# REV002.net
KiCad netlist of a schematic drawn in EAGLE
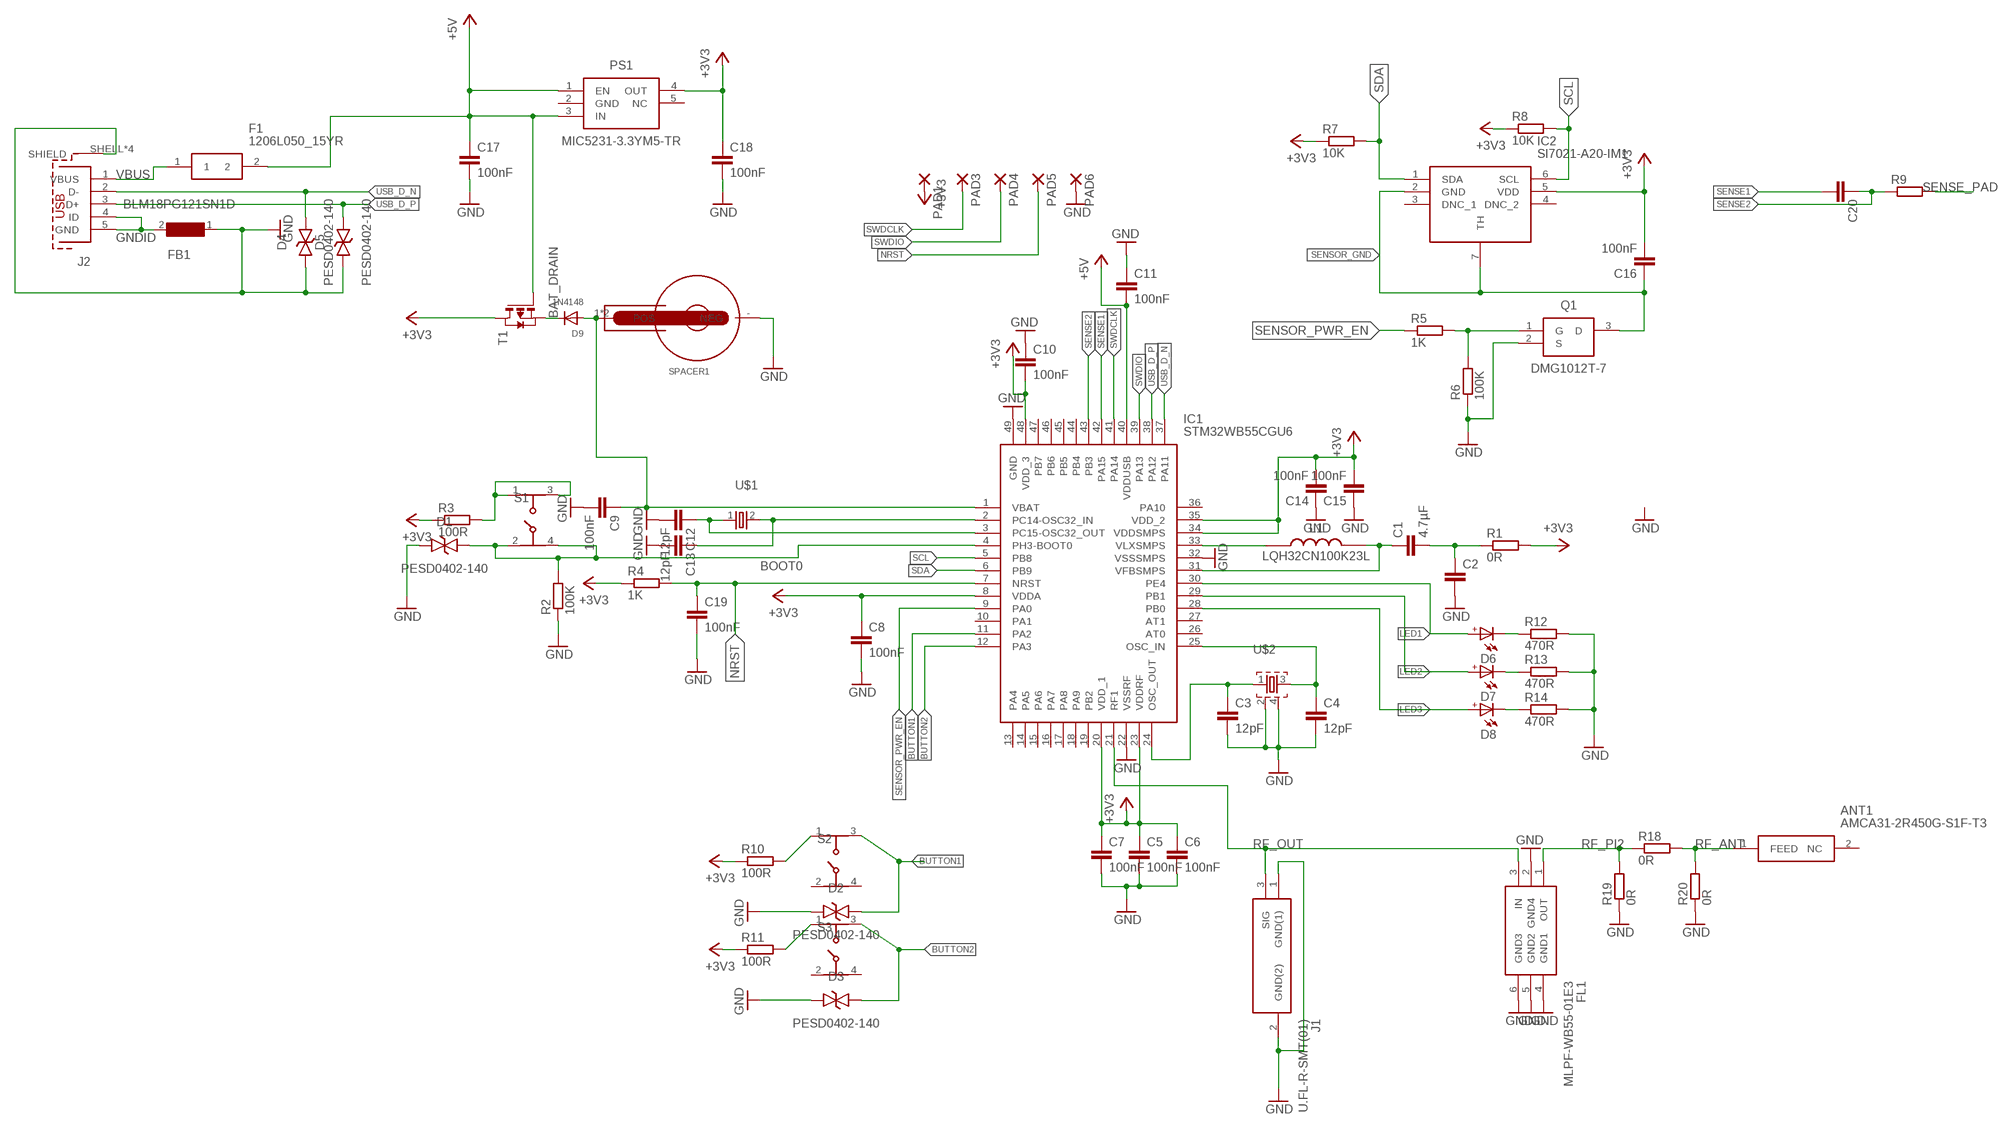
[diagram p0: schematic, sheet 1]

(export (version "E")
  (design (tool "Eeschema 10.0.6"))
  (components
    (comp (ref "ANT1")
      (value "AMCA31-2R450G-S1F-T3")
      (footprint "eagle-import:ANTC3216X140N")
      (libsource (lib "eagle-import") (part "AMCA31-2R450G-S1F-T3"))
    )
    (comp (ref "C1")
      (value "4.7µF")
      (footprint "eagle-import:C1210K")
      (libsource (lib "eagle-import") (part "C-EUC1210K"))
    )
    (comp (ref "C2")
      (value "C-EUC0402K")
      (footprint "eagle-import:C0402K")
      (libsource (lib "eagle-import") (part "C-EUC0402K"))
    )
    (comp (ref "C3")
      (value "12pF")
      (footprint "eagle-import:C0402K")
      (libsource (lib "eagle-import") (part "C-EUC0402K"))
    )
    (comp (ref "C4")
      (value "12pF")
      (footprint "eagle-import:C0402K")
      (libsource (lib "eagle-import") (part "C-EUC0402K"))
    )
    (comp (ref "C5")
      (value "100nF")
      (footprint "eagle-import:C0402K")
      (libsource (lib "eagle-import") (part "C-EUC0402K"))
    )
    (comp (ref "C6")
      (value "100nF")
      (footprint "eagle-import:C0402K")
      (libsource (lib "eagle-import") (part "C-EUC0402K"))
    )
    (comp (ref "C7")
      (value "100nF")
      (footprint "eagle-import:C0402K")
      (libsource (lib "eagle-import") (part "C-EUC0402K"))
    )
    (comp (ref "C8")
      (value "100nF")
      (footprint "eagle-import:C0402K")
      (libsource (lib "eagle-import") (part "C-EUC0402K"))
    )
    (comp (ref "C9")
      (value "100nF")
      (footprint "eagle-import:C0402K")
      (libsource (lib "eagle-import") (part "C-EUC0402K"))
    )
    (comp (ref "C10")
      (value "100nF")
      (footprint "eagle-import:C0402K")
      (libsource (lib "eagle-import") (part "C-EUC0402K"))
    )
    (comp (ref "C11")
      (value "100nF")
      (footprint "eagle-import:C0402K")
      (libsource (lib "eagle-import") (part "C-EUC0402K"))
    )
    (comp (ref "C12")
      (value "12pF")
      (footprint "eagle-import:C0402K")
      (libsource (lib "eagle-import") (part "C-EUC0402K"))
    )
    (comp (ref "C13")
      (value "12pF")
      (footprint "eagle-import:C0402K")
      (libsource (lib "eagle-import") (part "C-EUC0402K"))
    )
    (comp (ref "C14")
      (value "100nF")
      (footprint "eagle-import:C0402K")
      (libsource (lib "eagle-import") (part "C-EUC0402K"))
    )
    (comp (ref "C15")
      (value "100nF")
      (footprint "eagle-import:C0402K")
      (libsource (lib "eagle-import") (part "C-EUC0402K"))
    )
    (comp (ref "C16")
      (value "100nF")
      (footprint "eagle-import:C0402K")
      (libsource (lib "eagle-import") (part "C-EUC0402K"))
    )
    (comp (ref "C17")
      (value "100nF")
      (footprint "eagle-import:C0402K")
      (libsource (lib "eagle-import") (part "C-EUC0402K"))
    )
    (comp (ref "C18")
      (value "100nF")
      (footprint "eagle-import:C0402K")
      (libsource (lib "eagle-import") (part "C-EUC0402K"))
    )
    (comp (ref "C19")
      (value "100nF")
      (footprint "eagle-import:C0402K")
      (libsource (lib "eagle-import") (part "C-EUC0402K"))
    )
    (comp (ref "C20")
      (value "C-EUC0402K")
      (footprint "eagle-import:C0402K")
      (libsource (lib "eagle-import") (part "C-EUC0402K"))
    )
    (comp (ref "D1")
      (value "PESD0402-140")
      (footprint "eagle-import:DIONC1005X43N")
      (fields (field (name "RS_PART_NUMBER") "7192294"))
      (libsource (lib "eagle-import") (part "PESD0402-140"))
    )
    (comp (ref "D2")
      (value "PESD0402-140")
      (footprint "eagle-import:DIONC1005X43N")
      (fields (field (name "RS_PART_NUMBER") "7192294"))
      (libsource (lib "eagle-import") (part "PESD0402-140"))
    )
    (comp (ref "D3")
      (value "PESD0402-140")
      (footprint "eagle-import:DIONC1005X43N")
      (fields (field (name "RS_PART_NUMBER") "7192294"))
      (libsource (lib "eagle-import") (part "PESD0402-140"))
    )
    (comp (ref "D4")
      (value "PESD0402-140")
      (footprint "eagle-import:DIONC1005X43N")
      (fields (field (name "RS_PART_NUMBER") "7192294"))
      (libsource (lib "eagle-import") (part "PESD0402-140"))
    )
    (comp (ref "D5")
      (value "PESD0402-140")
      (footprint "eagle-import:DIONC1005X43N")
      (fields (field (name "RS_PART_NUMBER") "7192294"))
      (libsource (lib "eagle-import") (part "PESD0402-140"))
    )
    (comp (ref "D6")
      (value "WL-SMCD_0603_150060BS55040")
      (footprint "eagle-import:WL-SMCD_0603")
      (libsource (lib "eagle-import") (part "WL-SMCD_0603_150060BS55040"))
    )
    (comp (ref "D7")
      (value "WL-SMCD_0603_150060BS55040")
      (footprint "eagle-import:WL-SMCD_0603")
      (libsource (lib "eagle-import") (part "WL-SMCD_0603_150060BS55040"))
    )
    (comp (ref "D8")
      (value "WL-SMCD_0603_150060BS55040")
      (footprint "eagle-import:WL-SMCD_0603")
      (libsource (lib "eagle-import") (part "WL-SMCD_0603_150060BS55040"))
    )
    (comp (ref "D9")
      (value "1N4148")
      (footprint "eagle-import:SOD-323F")
      (libsource (lib "eagle-import") (part "DIODESOD-323F"))
    )
    (comp (ref "F1")
      (value "1206L050_15YR")
      (footprint "eagle-import:FUSC3216X75N")
      (fields
        (field (name "MANUFACTURER_PART_NUMBER") "1206L050/15YR")
        (field (name "MOUSER_PART_NUMBER") "576-1206L050/15YR")
        (field (name "RS_PART_NUMBER") "1740347")
      )
      (libsource (lib "eagle-import") (part "1206L050_15YR"))
    )
    (comp (ref "FB1")
      (value "BLM18PG121SN1D")
      (footprint "eagle-import:BEADC1608X95N")
      (fields (field (name "RS_PART_NUMBER") "7241380P"))
      (libsource (lib "eagle-import") (part "BLM18PG121SN1D"))
    )
    (comp (ref "FL1")
      (value "MLPF-WB55-01E3")
      (footprint "eagle-import:MLPFWB5501E3")
      (fields (field (name "MOUSER_PART_NUMBER") "511-MLPF-WB55-01E3"))
      (libsource (lib "eagle-import") (part "MLPF-WB55-01E3"))
    )
    (comp (ref "IC1")
      (value "STM32WB55CGU6")
      (footprint "eagle-import:QFN50P700X700X65-49N")
      (fields (field (name "MOUSER_PART_NUMBER") "511-STM32WB55CGU6"))
      (libsource (lib "eagle-import") (part "STM32WB55CGU6"))
    )
    (comp (ref "IC2")
      (value "SI7021-A20-IM1")
      (footprint "eagle-import:SON100P300X300X121-7N")
      (fields
        (field (name "MANUFACTURER_PART_NUMBER") "Si7021-A20-IM1")
        (field (name "MOUSER_PART_NUMBER") "634-SI7021-A20-IM1")
        (field (name "RS_PART_NUMBER") "8652325P")
      )
      (libsource (lib "eagle-import") (part "SI7021-A20-IM1"))
    )
    (comp (ref "J1")
      (value "U.FL-R-SMT(01)")
      (footprint "eagle-import:U.FL-R-SMT(01)")
      (fields (field (name "RS_PART_NUMBER") "4812324"))
      (libsource (lib "eagle-import") (part "U.FL-R-SMT(01)"))
    )
    (comp (ref "J2")
      (value "629105136821")
      (footprint "eagle-import:629105136821")
      (libsource (lib "eagle-import") (part "629105136821"))
    )
    (comp (ref "L1")
      (value "LQH32CN100K23L")
      (footprint "eagle-import:INDPM3225X220N")
      (fields (field (name "RS_PART_NUMBER") "4811882"))
      (libsource (lib "eagle-import") (part "LQH32CN100K23L"))
    )
    (comp (ref "PAD1")
      (value "SMD2")
      (footprint "eagle-import:SMD1,27-2,54")
      (libsource (lib "eagle-import") (part "SMD2"))
    )
    (comp (ref "PAD3")
      (value "SMD2")
      (footprint "eagle-import:SMD1,27-2,54")
      (libsource (lib "eagle-import") (part "SMD2"))
    )
    (comp (ref "PAD4")
      (value "SMD2")
      (footprint "eagle-import:SMD1,27-2,54")
      (libsource (lib "eagle-import") (part "SMD2"))
    )
    (comp (ref "PAD5")
      (value "SMD2")
      (footprint "eagle-import:SMD1,27-2,54")
      (libsource (lib "eagle-import") (part "SMD2"))
    )
    (comp (ref "PAD6")
      (value "SMD2")
      (footprint "eagle-import:SMD1,27-2,54")
      (libsource (lib "eagle-import") (part "SMD2"))
    )
    (comp (ref "PS1")
      (value "MIC5231-3.3YM5-TR")
      (footprint "eagle-import:SOT95P270X145-5N")
      (libsource (lib "eagle-import") (part "MIC5231-3.3YM5-TR"))
    )
    (comp (ref "Q1")
      (value "DMG1012T-7")
      (footprint "eagle-import:SOT50P160X80-3N")
      (fields (field (name "RS_PART_NUMBER") "7514064"))
      (libsource (lib "eagle-import") (part "DMG1012T-7"))
    )
    (comp (ref "R1")
      (value "0R")
      (footprint "eagle-import:R0402")
      (libsource (lib "eagle-import") (part "R-EU_R0402"))
    )
    (comp (ref "R2")
      (value "100K")
      (footprint "eagle-import:R0402")
      (libsource (lib "eagle-import") (part "R-EU_R0402"))
    )
    (comp (ref "R3")
      (value "100R")
      (footprint "eagle-import:R0402")
      (libsource (lib "eagle-import") (part "R-EU_R0402"))
    )
    (comp (ref "R4")
      (value "1K")
      (footprint "eagle-import:R0402")
      (libsource (lib "eagle-import") (part "R-EU_R0402"))
    )
    (comp (ref "R5")
      (value "1K")
      (footprint "eagle-import:R0402")
      (libsource (lib "eagle-import") (part "R-EU_R0402"))
    )
    (comp (ref "R6")
      (value "100K")
      (footprint "eagle-import:R0402")
      (libsource (lib "eagle-import") (part "R-EU_R0402"))
    )
    (comp (ref "R7")
      (value "10K")
      (footprint "eagle-import:R0402")
      (libsource (lib "eagle-import") (part "R-EU_R0402"))
    )
    (comp (ref "R8")
      (value "10K")
      (footprint "eagle-import:R0402")
      (libsource (lib "eagle-import") (part "R-EU_R0402"))
    )
    (comp (ref "R9")
      (value "R-EU_R0402")
      (footprint "eagle-import:R0402")
      (libsource (lib "eagle-import") (part "R-EU_R0402"))
    )
    (comp (ref "R10")
      (value "100R")
      (footprint "eagle-import:R0402")
      (libsource (lib "eagle-import") (part "R-EU_R0402"))
    )
    (comp (ref "R11")
      (value "100R")
      (footprint "eagle-import:R0402")
      (libsource (lib "eagle-import") (part "R-EU_R0402"))
    )
    (comp (ref "R12")
      (value "470R")
      (footprint "eagle-import:R0402")
      (libsource (lib "eagle-import") (part "R-EU_R0402"))
    )
    (comp (ref "R13")
      (value "470R")
      (footprint "eagle-import:R0402")
      (libsource (lib "eagle-import") (part "R-EU_R0402"))
    )
    (comp (ref "R14")
      (value "470R")
      (footprint "eagle-import:R0402")
      (libsource (lib "eagle-import") (part "R-EU_R0402"))
    )
    (comp (ref "R18")
      (value "0R")
      (footprint "eagle-import:R0402")
      (libsource (lib "eagle-import") (part "R-EU_R0402"))
    )
    (comp (ref "R19")
      (value "0R")
      (footprint "eagle-import:R0402")
      (libsource (lib "eagle-import") (part "R-EU_R0402"))
    )
    (comp (ref "R20")
      (value "0R")
      (footprint "eagle-import:R0402")
      (libsource (lib "eagle-import") (part "R-EU_R0402"))
    )
    (comp (ref "S1")
      (value "434153017835")
      (footprint "eagle-import:434153017835")
      (libsource (lib "eagle-import") (part "434153017835"))
    )
    (comp (ref "S2")
      (value "434153017835")
      (footprint "eagle-import:434153017835")
      (libsource (lib "eagle-import") (part "434153017835"))
    )
    (comp (ref "S3")
      (value "434153017835")
      (footprint "eagle-import:434153017835")
      (libsource (lib "eagle-import") (part "434153017835"))
    )
    (comp (ref "SPACER1")
      (value "WA-BCMC_SMT_79523141")
      (footprint "eagle-import:79523141")
      (libsource (lib "eagle-import") (part "WA-BCMC_SMT_79523141"))
    )
    (comp (ref "T1")
      (value "PMOSSOT23")
      (footprint "eagle-import:SOT-23")
      (libsource (lib "eagle-import") (part "PMOSSOT23"))
    )
    (comp (ref "U$1")
      (value "XTAL_32KHZ")
      (footprint "eagle-import:XTAL_3215_N")
      (libsource (lib "eagle-import") (part "XTAL_32KHZ"))
    )
    (comp (ref "U$2")
      (value "XTAL_32MHZ")
      (footprint "eagle-import:BT-XTAL_2016_N")
      (libsource (lib "eagle-import") (part "XTAL_32MHZ"))
    )
  )
  (nets
    (net (code "1") (name "+3V3") (class "Default")
      (node (ref "C10") (pin "2") (pinfunction "2_2") (pintype "passive"))
      (node (ref "C14") (pin "2") (pinfunction "2_2") (pintype "passive"))
      (node (ref "C15") (pin "2") (pinfunction "2_2") (pintype "passive"))
      (node (ref "C16") (pin "2") (pinfunction "2_2") (pintype "passive"))
      (node (ref "C18") (pin "1") (pinfunction "1_1") (pintype "passive"))
      (node (ref "C5") (pin "1") (pinfunction "1_1") (pintype "passive"))
      (node (ref "C6") (pin "1") (pinfunction "1_1") (pintype "passive"))
      (node (ref "C7") (pin "1") (pinfunction "1_1") (pintype "passive"))
      (node (ref "C8") (pin "1") (pinfunction "1_1") (pintype "passive"))
      (node (ref "IC1") (pin "20") (pinfunction "VDD_1_20") (pintype "bidirectional"))
      (node (ref "IC1") (pin "23") (pinfunction "VDDRF_23") (pintype "bidirectional"))
      (node (ref "IC1") (pin "34") (pinfunction "VDDSMPS_34") (pintype "bidirectional"))
      (node (ref "IC1") (pin "35") (pinfunction "VDD_2_35") (pintype "bidirectional"))
      (node (ref "IC1") (pin "48") (pinfunction "VDD_3_48") (pintype "bidirectional"))
      (node (ref "IC1") (pin "8") (pinfunction "VDDA_8") (pintype "bidirectional"))
      (node (ref "IC2") (pin "5") (pinfunction "VDD_5") (pintype "bidirectional"))
      (node (ref "PAD1") (pin "1") (pinfunction "P_1") (pintype "passive"))
      (node (ref "PS1") (pin "4") (pinfunction "OUT_4") (pintype "input"))
      (node (ref "R1") (pin "2") (pinfunction "2_2") (pintype "passive"))
      (node (ref "R10") (pin "1") (pinfunction "1_1") (pintype "passive"))
      (node (ref "R11") (pin "1") (pinfunction "1_1") (pintype "passive"))
      (node (ref "R3") (pin "1") (pinfunction "1_1") (pintype "passive"))
      (node (ref "R4") (pin "1") (pinfunction "1_1") (pintype "passive"))
      (node (ref "R7") (pin "1") (pinfunction "1_1") (pintype "passive"))
      (node (ref "R8") (pin "1") (pinfunction "1_1") (pintype "passive"))
      (node (ref "T1") (pin "1") (pinfunction "D_1") (pintype "passive"))
    )
    (net (code "2") (name "+5V") (class "Default")
      (node (ref "C11") (pin "2") (pinfunction "2_2") (pintype "passive"))
      (node (ref "C17") (pin "1") (pinfunction "1_1") (pintype "passive"))
      (node (ref "F1") (pin "2") (pinfunction "2_2") (pintype "bidirectional"))
      (node (ref "IC1") (pin "40") (pinfunction "VDDUSB_40") (pintype "bidirectional"))
      (node (ref "PS1") (pin "1") (pinfunction "EN_1") (pintype "input"))
      (node (ref "PS1") (pin "3") (pinfunction "IN_3") (pintype "input"))
      (node (ref "T1") (pin "3") (pinfunction "G_3") (pintype "passive"))
    )
    (net (code "3") (name "/BAT_DRAIN") (class "Default")
      (node (ref "D9") (pin "C") (pinfunction "C_C") (pintype "passive"))
      (node (ref "T1") (pin "2") (pinfunction "S_2") (pintype "passive"))
    )
    (net (code "4") (name "/BOOT0") (class "Default")
      (node (ref "D1") (pin "2") (pinfunction "A_2") (pintype "bidirectional"))
      (node (ref "IC1") (pin "4") (pinfunction "PH3-BOOT0_4") (pintype "bidirectional"))
      (node (ref "R2") (pin "2") (pinfunction "2_2") (pintype "passive"))
      (node (ref "S1") (pin "2") (pinfunction "3_2") (pintype "passive"))
      (node (ref "S1") (pin "4") (pinfunction "4_4") (pintype "passive"))
    )
    (net (code "5") (name "/GNDID") (class "Default")
      (node (ref "FB1") (pin "2") (pinfunction "2_2") (pintype "passive"))
      (node (ref "J2") (pin "4") (pinfunction "ID_4") (pintype "passive"))
      (node (ref "J2") (pin "5") (pinfunction "GND_5") (pintype "passive"))
    )
    (net (code "6") (name "/RF_ANT") (class "Default")
      (node (ref "ANT1") (pin "1") (pinfunction "FEED_1") (pintype "input"))
      (node (ref "R18") (pin "2") (pinfunction "2_2") (pintype "passive"))
      (node (ref "R20") (pin "2") (pinfunction "2_2") (pintype "passive"))
    )
    (net (code "7") (name "/RF_OUT") (class "Default")
      (node (ref "FL1") (pin "3") (pinfunction "IN_3") (pintype "bidirectional"))
      (node (ref "IC1") (pin "21") (pinfunction "RF1_21") (pintype "bidirectional"))
      (node (ref "J1") (pin "3") (pinfunction "SIG_3") (pintype "bidirectional"))
    )
    (net (code "8") (name "/RF_PI2") (class "Default")
      (node (ref "FL1") (pin "1") (pinfunction "OUT_1") (pintype "bidirectional"))
      (node (ref "R18") (pin "1") (pinfunction "1_1") (pintype "passive"))
      (node (ref "R19") (pin "2") (pinfunction "2_2") (pintype "passive"))
    )
    (net (code "9") (name "/SENSE_PAD") (class "Default")
      (node (ref "R9") (pin "2") (pinfunction "2_2") (pintype "passive"))
    )
    (net (code "10") (name "/VBUS") (class "Default")
      (node (ref "F1") (pin "1") (pinfunction "1_1") (pintype "bidirectional"))
      (node (ref "J2") (pin "1") (pinfunction "VBUS_1") (pintype "passive"))
    )
    (net (code "11") (name "BUTTON1") (class "Default")
      (node (ref "D2") (pin "2") (pinfunction "A_2") (pintype "bidirectional"))
      (node (ref "IC1") (pin "11") (pinfunction "PA2_11") (pintype "bidirectional"))
      (node (ref "S2") (pin "3") (pinfunction "2_3") (pintype "passive"))
    )
    (net (code "12") (name "BUTTON2") (class "Default")
      (node (ref "D3") (pin "2") (pinfunction "A_2") (pintype "bidirectional"))
      (node (ref "IC1") (pin "12") (pinfunction "PA3_12") (pintype "bidirectional"))
      (node (ref "S3") (pin "3") (pinfunction "2_3") (pintype "passive"))
    )
    (net (code "13") (name "GND") (class "Default")
      (node (ref "C10") (pin "1") (pinfunction "1_1") (pintype "passive"))
      (node (ref "C11") (pin "1") (pinfunction "1_1") (pintype "passive"))
      (node (ref "C12") (pin "2") (pinfunction "2_2") (pintype "passive"))
      (node (ref "C13") (pin "2") (pinfunction "2_2") (pintype "passive"))
      (node (ref "C14") (pin "1") (pinfunction "1_1") (pintype "passive"))
      (node (ref "C15") (pin "1") (pinfunction "1_1") (pintype "passive"))
      (node (ref "C17") (pin "2") (pinfunction "2_2") (pintype "passive"))
      (node (ref "C18") (pin "2") (pinfunction "2_2") (pintype "passive"))
      (node (ref "C19") (pin "2") (pinfunction "2_2") (pintype "passive"))
      (node (ref "C2") (pin "2") (pinfunction "2_2") (pintype "passive"))
      (node (ref "C3") (pin "2") (pinfunction "2_2") (pintype "passive"))
      (node (ref "C4") (pin "2") (pinfunction "2_2") (pintype "passive"))
      (node (ref "C5") (pin "2") (pinfunction "2_2") (pintype "passive"))
      (node (ref "C6") (pin "2") (pinfunction "2_2") (pintype "passive"))
      (node (ref "C7") (pin "2") (pinfunction "2_2") (pintype "passive"))
      (node (ref "C8") (pin "2") (pinfunction "2_2") (pintype "passive"))
      (node (ref "C9") (pin "2") (pinfunction "2_2") (pintype "passive"))
      (node (ref "D1") (pin "1") (pinfunction "K_1") (pintype "bidirectional"))
      (node (ref "D2") (pin "1") (pinfunction "K_1") (pintype "bidirectional"))
      (node (ref "D3") (pin "1") (pinfunction "K_1") (pintype "bidirectional"))
      (node (ref "D4") (pin "1") (pinfunction "K_1") (pintype "bidirectional"))
      (node (ref "D5") (pin "1") (pinfunction "K_1") (pintype "bidirectional"))
      (node (ref "FB1") (pin "1") (pinfunction "1_1") (pintype "passive"))
      (node (ref "FL1") (pin "2") (pinfunction "GND4_2") (pintype "bidirectional"))
      (node (ref "FL1") (pin "4") (pinfunction "GND1_4") (pintype "bidirectional"))
      (node (ref "FL1") (pin "5") (pinfunction "GND2_5") (pintype "bidirectional"))
      (node (ref "FL1") (pin "6") (pinfunction "GND3_6") (pintype "bidirectional"))
      (node (ref "IC1") (pin "22") (pinfunction "VSSRF_22") (pintype "bidirectional"))
      (node (ref "IC1") (pin "32") (pinfunction "VSSSMPS_32") (pintype "bidirectional"))
      (node (ref "IC1") (pin "49") (pinfunction "GND_49") (pintype "bidirectional"))
      (node (ref "J1") (pin "1") (pinfunction "GND(1)_1") (pintype "bidirectional"))
      (node (ref "J1") (pin "2") (pinfunction "GND(2)_2") (pintype "bidirectional"))
      (node (ref "J2") (pin "SHELL") (pinfunction "SHIELD_SHELL") (pintype "passive"))
      (node (ref "J2") (pin "SHELL1") (pinfunction "SHIELD_SHELL1") (pintype "passive"))
      (node (ref "J2") (pin "SHELL2") (pinfunction "SHIELD_SHELL2") (pintype "passive"))
      (node (ref "J2") (pin "SHELL3") (pinfunction "SHIELD_SHELL3") (pintype "passive"))
      (node (ref "PAD6") (pin "1") (pinfunction "P_1") (pintype "passive"))
      (node (ref "Q1") (pin "2") (pinfunction "S_2") (pintype "passive"))
      (node (ref "R12") (pin "2") (pinfunction "2_2") (pintype "passive"))
      (node (ref "R13") (pin "2") (pinfunction "2_2") (pintype "passive"))
      (node (ref "R14") (pin "2") (pinfunction "2_2") (pintype "passive"))
      (node (ref "R19") (pin "1") (pinfunction "1_1") (pintype "passive"))
      (node (ref "R2") (pin "1") (pinfunction "1_1") (pintype "passive"))
      (node (ref "R20") (pin "1") (pinfunction "1_1") (pintype "passive"))
      (node (ref "R6") (pin "1") (pinfunction "1_1") (pintype "passive"))
      (node (ref "SPACER1") (pin "-") (pinfunction "NEG_-") (pintype "bidirectional"))
      (node (ref "U$2") (pin "2") (pinfunction "2_2") (pintype "passive"))
      (node (ref "U$2") (pin "4") (pinfunction "4_4") (pintype "passive"))
    )
    (net (code "14") (name "LED1") (class "Default")
      (node (ref "D6") (pin "2") (pinfunction "A_2") (pintype "passive"))
      (node (ref "IC1") (pin "30") (pinfunction "PE4_30") (pintype "bidirectional"))
    )
    (net (code "15") (name "LED2") (class "Default")
      (node (ref "D7") (pin "2") (pinfunction "A_2") (pintype "passive"))
      (node (ref "IC1") (pin "29") (pinfunction "PB1_29") (pintype "bidirectional"))
    )
    (net (code "16") (name "LED3") (class "Default")
      (node (ref "D8") (pin "2") (pinfunction "A_2") (pintype "passive"))
      (node (ref "IC1") (pin "28") (pinfunction "PB0_28") (pintype "bidirectional"))
    )
    (net (code "17") (name "NRST") (class "Default")
      (node (ref "C19") (pin "1") (pinfunction "1_1") (pintype "passive"))
      (node (ref "IC1") (pin "7") (pinfunction "NRST_7") (pintype "bidirectional"))
      (node (ref "PAD5") (pin "1") (pinfunction "P_1") (pintype "passive"))
      (node (ref "R4") (pin "2") (pinfunction "2_2") (pintype "passive"))
    )
    (net (code "18") (name "Net-(C1-Pad2)") (class "Default")
      (node (ref "C1") (pin "2") (pinfunction "2_2") (pintype "passive"))
      (node (ref "C2") (pin "1") (pinfunction "1_1") (pintype "passive"))
      (node (ref "R1") (pin "1") (pinfunction "1_1") (pintype "passive"))
    )
    (net (code "19") (name "Net-(D6-C)") (class "Default")
      (node (ref "D6") (pin "1") (pinfunction "C_1") (pintype "passive"))
      (node (ref "R12") (pin "1") (pinfunction "1_1") (pintype "passive"))
    )
    (net (code "20") (name "Net-(D7-C)") (class "Default")
      (node (ref "D7") (pin "1") (pinfunction "C_1") (pintype "passive"))
      (node (ref "R13") (pin "1") (pinfunction "1_1") (pintype "passive"))
    )
    (net (code "21") (name "Net-(D8-C)") (class "Default")
      (node (ref "D8") (pin "1") (pinfunction "C_1") (pintype "passive"))
      (node (ref "R14") (pin "1") (pinfunction "1_1") (pintype "passive"))
    )
    (net (code "22") (name "Net-(IC1-OSC_IN)") (class "Default")
      (node (ref "C4") (pin "1") (pinfunction "1_1") (pintype "passive"))
      (node (ref "IC1") (pin "25") (pinfunction "OSC_IN_25") (pintype "bidirectional"))
      (node (ref "U$2") (pin "3") (pinfunction "3_3") (pintype "passive"))
    )
    (net (code "23") (name "Net-(IC1-OSC_OUT)") (class "Default")
      (node (ref "C3") (pin "1") (pinfunction "1_1") (pintype "passive"))
      (node (ref "IC1") (pin "24") (pinfunction "OSC_OUT_24") (pintype "bidirectional"))
      (node (ref "U$2") (pin "1") (pinfunction "1_1") (pintype "passive"))
    )
    (net (code "24") (name "Net-(IC1-PC14-OSC32_IN)") (class "Default")
      (node (ref "C13") (pin "1") (pinfunction "1_1") (pintype "passive"))
      (node (ref "IC1") (pin "2") (pinfunction "PC14-OSC32_IN_2") (pintype "bidirectional"))
      (node (ref "U$1") (pin "2") (pinfunction "2_2") (pintype "passive"))
    )
    (net (code "25") (name "Net-(IC1-PC15-OSC32_OUT)") (class "Default")
      (node (ref "C12") (pin "1") (pinfunction "1_1") (pintype "passive"))
      (node (ref "IC1") (pin "3") (pinfunction "PC15-OSC32_OUT_3") (pintype "bidirectional"))
      (node (ref "U$1") (pin "1") (pinfunction "1_1") (pintype "passive"))
    )
    (net (code "26") (name "Net-(IC1-VBAT)") (class "Default")
      (node (ref "C9") (pin "1") (pinfunction "1_1") (pintype "passive"))
      (node (ref "D9") (pin "A") (pinfunction "A_A") (pintype "passive"))
      (node (ref "IC1") (pin "1") (pinfunction "VBAT_1") (pintype "bidirectional"))
      (node (ref "SPACER1") (pin "1") (pinfunction "POS_1") (pintype "bidirectional"))
      (node (ref "SPACER1") (pin "2") (pinfunction "POS_2") (pintype "bidirectional"))
    )
    (net (code "27") (name "Net-(IC1-VFBSMPS)") (class "Default")
      (node (ref "C1") (pin "1") (pinfunction "1_1") (pintype "passive"))
      (node (ref "IC1") (pin "31") (pinfunction "VFBSMPS_31") (pintype "bidirectional"))
      (node (ref "L1") (pin "2") (pinfunction "2_2") (pintype "bidirectional"))
    )
    (net (code "28") (name "Net-(IC1-VLXSMPS)") (class "Default")
      (node (ref "IC1") (pin "33") (pinfunction "VLXSMPS_33") (pintype "bidirectional"))
      (node (ref "L1") (pin "1") (pinfunction "1_1") (pintype "bidirectional"))
    )
    (net (code "29") (name "Net-(Q1-G)") (class "Default")
      (node (ref "Q1") (pin "1") (pinfunction "G_1") (pintype "passive"))
      (node (ref "R5") (pin "2") (pinfunction "2_2") (pintype "passive"))
      (node (ref "R6") (pin "2") (pinfunction "2_2") (pintype "passive"))
    )
    (net (code "30") (name "Net-(R10-Pad2)") (class "Default")
      (node (ref "R10") (pin "2") (pinfunction "2_2") (pintype "passive"))
      (node (ref "S2") (pin "1") (pinfunction "1_1") (pintype "passive"))
    )
    (net (code "31") (name "Net-(R11-Pad2)") (class "Default")
      (node (ref "R11") (pin "2") (pinfunction "2_2") (pintype "passive"))
      (node (ref "S3") (pin "1") (pinfunction "1_1") (pintype "passive"))
    )
    (net (code "32") (name "Net-(S1-2)") (class "Default")
      (node (ref "R3") (pin "2") (pinfunction "2_2") (pintype "passive"))
      (node (ref "S1") (pin "1") (pinfunction "1_1") (pintype "passive"))
      (node (ref "S1") (pin "3") (pinfunction "2_3") (pintype "passive"))
    )
    (net (code "33") (name "SCL") (class "Default")
      (node (ref "IC1") (pin "5") (pinfunction "PB8_5") (pintype "bidirectional"))
      (node (ref "IC2") (pin "6") (pinfunction "SCL_6") (pintype "bidirectional"))
      (node (ref "R8") (pin "2") (pinfunction "2_2") (pintype "passive"))
    )
    (net (code "34") (name "SDA") (class "Default")
      (node (ref "IC1") (pin "6") (pinfunction "PB9_6") (pintype "bidirectional"))
      (node (ref "IC2") (pin "1") (pinfunction "SDA_1") (pintype "bidirectional"))
      (node (ref "R7") (pin "2") (pinfunction "2_2") (pintype "passive"))
    )
    (net (code "35") (name "SENSE1") (class "Default")
      (node (ref "C20") (pin "2") (pinfunction "2_2") (pintype "passive"))
      (node (ref "IC1") (pin "42") (pinfunction "PA15_42") (pintype "bidirectional"))
    )
    (net (code "36") (name "SENSE2") (class "Default")
      (node (ref "C20") (pin "1") (pinfunction "1_1") (pintype "passive"))
      (node (ref "IC1") (pin "43") (pinfunction "PB3_43") (pintype "bidirectional"))
      (node (ref "R9") (pin "1") (pinfunction "1_1") (pintype "passive"))
    )
    (net (code "37") (name "SENSOR_GND") (class "Default")
      (node (ref "C16") (pin "1") (pinfunction "1_1") (pintype "passive"))
      (node (ref "IC2") (pin "2") (pinfunction "GND_2") (pintype "bidirectional"))
      (node (ref "IC2") (pin "7") (pinfunction "TH_7") (pintype "bidirectional"))
      (node (ref "Q1") (pin "3") (pinfunction "D_3") (pintype "passive"))
    )
    (net (code "38") (name "SENSOR_PWR_EN") (class "Default")
      (node (ref "IC1") (pin "9") (pinfunction "PA0_9") (pintype "bidirectional"))
      (node (ref "R5") (pin "1") (pinfunction "1_1") (pintype "passive"))
    )
    (net (code "39") (name "SWDCLK") (class "Default")
      (node (ref "IC1") (pin "41") (pinfunction "PA14_41") (pintype "bidirectional"))
      (node (ref "PAD3") (pin "1") (pinfunction "P_1") (pintype "passive"))
    )
    (net (code "40") (name "SWDIO") (class "Default")
      (node (ref "IC1") (pin "39") (pinfunction "PA13_39") (pintype "bidirectional"))
      (node (ref "PAD4") (pin "1") (pinfunction "P_1") (pintype "passive"))
    )
    (net (code "41") (name "USB_D_N") (class "Default")
      (node (ref "D4") (pin "2") (pinfunction "A_2") (pintype "bidirectional"))
      (node (ref "IC1") (pin "37") (pinfunction "PA11_37") (pintype "bidirectional"))
      (node (ref "J2") (pin "2") (pinfunction "D-_2") (pintype "passive"))
    )
    (net (code "42") (name "USB_D_P") (class "Default")
      (node (ref "D5") (pin "2") (pinfunction "A_2") (pintype "bidirectional"))
      (node (ref "IC1") (pin "38") (pinfunction "PA12_38") (pintype "bidirectional"))
      (node (ref "J2") (pin "3") (pinfunction "D+_3") (pintype "passive"))
    )
    (net (code "43") (name "unconnected-(ANT1-NC-Pad2)") (class "Default")
      (node (ref "ANT1") (pin "2") (pinfunction "NC_2") (pintype "no_connect"))
    )
    (net (code "44") (name "unconnected-(IC1-AT0-Pad26)") (class "Default")
      (node (ref "IC1") (pin "26") (pinfunction "AT0_26") (pintype "bidirectional"))
    )
    (net (code "45") (name "unconnected-(IC1-AT1-Pad27)") (class "Default")
      (node (ref "IC1") (pin "27") (pinfunction "AT1_27") (pintype "bidirectional"))
    )
    (net (code "46") (name "unconnected-(IC1-PA1-Pad10)") (class "Default")
      (node (ref "IC1") (pin "10") (pinfunction "PA1_10") (pintype "bidirectional"))
    )
    (net (code "47") (name "unconnected-(IC1-PA4-Pad13)") (class "Default")
      (node (ref "IC1") (pin "13") (pinfunction "PA4_13") (pintype "bidirectional"))
    )
    (net (code "48") (name "unconnected-(IC1-PA5-Pad14)") (class "Default")
      (node (ref "IC1") (pin "14") (pinfunction "PA5_14") (pintype "bidirectional"))
    )
    (net (code "49") (name "unconnected-(IC1-PA6-Pad15)") (class "Default")
      (node (ref "IC1") (pin "15") (pinfunction "PA6_15") (pintype "bidirectional"))
    )
    (net (code "50") (name "unconnected-(IC1-PA7-Pad16)") (class "Default")
      (node (ref "IC1") (pin "16") (pinfunction "PA7_16") (pintype "bidirectional"))
    )
    (net (code "51") (name "unconnected-(IC1-PA8-Pad17)") (class "Default")
      (node (ref "IC1") (pin "17") (pinfunction "PA8_17") (pintype "bidirectional"))
    )
    (net (code "52") (name "unconnected-(IC1-PA9-Pad18)") (class "Default")
      (node (ref "IC1") (pin "18") (pinfunction "PA9_18") (pintype "bidirectional"))
    )
    (net (code "53") (name "unconnected-(IC1-PA10-Pad36)") (class "Default")
      (node (ref "IC1") (pin "36") (pinfunction "PA10_36") (pintype "bidirectional"))
    )
    (net (code "54") (name "unconnected-(IC1-PB2-Pad19)") (class "Default")
      (node (ref "IC1") (pin "19") (pinfunction "PB2_19") (pintype "bidirectional"))
    )
    (net (code "55") (name "unconnected-(IC1-PB4-Pad44)") (class "Default")
      (node (ref "IC1") (pin "44") (pinfunction "PB4_44") (pintype "bidirectional"))
    )
    (net (code "56") (name "unconnected-(IC1-PB5-Pad45)") (class "Default")
      (node (ref "IC1") (pin "45") (pinfunction "PB5_45") (pintype "bidirectional"))
    )
    (net (code "57") (name "unconnected-(IC1-PB6-Pad46)") (class "Default")
      (node (ref "IC1") (pin "46") (pinfunction "PB6_46") (pintype "bidirectional"))
    )
    (net (code "58") (name "unconnected-(IC1-PB7-Pad47)") (class "Default")
      (node (ref "IC1") (pin "47") (pinfunction "PB7_47") (pintype "bidirectional"))
    )
    (net (code "59") (name "unconnected-(IC2-DNC_1-Pad3)") (class "Default")
      (node (ref "IC2") (pin "3") (pinfunction "DNC_1_3") (pintype "bidirectional"))
    )
    (net (code "60") (name "unconnected-(IC2-DNC_2-Pad4)") (class "Default")
      (node (ref "IC2") (pin "4") (pinfunction "DNC_2_4") (pintype "bidirectional"))
    )
    (net (code "61") (name "unconnected-(PS1-GND-Pad2)") (class "Default")
      (node (ref "PS1") (pin "2") (pinfunction "GND_2") (pintype "input"))
    )
    (net (code "62") (name "unconnected-(PS1-NC-Pad5)") (class "Default")
      (node (ref "PS1") (pin "5") (pinfunction "NC_5") (pintype "input"))
    )
    (net (code "63") (name "unconnected-(S2-3-Pad2)") (class "Default")
      (node (ref "S2") (pin "2") (pinfunction "3_2") (pintype "passive"))
    )
    (net (code "64") (name "unconnected-(S2-Pad4)") (class "Default")
      (node (ref "S2") (pin "4") (pinfunction "4_4") (pintype "passive"))
    )
    (net (code "65") (name "unconnected-(S3-3-Pad2)") (class "Default")
      (node (ref "S3") (pin "2") (pinfunction "3_2") (pintype "passive"))
    )
    (net (code "66") (name "unconnected-(S3-Pad4)") (class "Default")
      (node (ref "S3") (pin "4") (pinfunction "4_4") (pintype "passive"))
    )
  )
)
